# AD_IanFritz.net
KiCad netlist of a schematic drawn in EAGLE
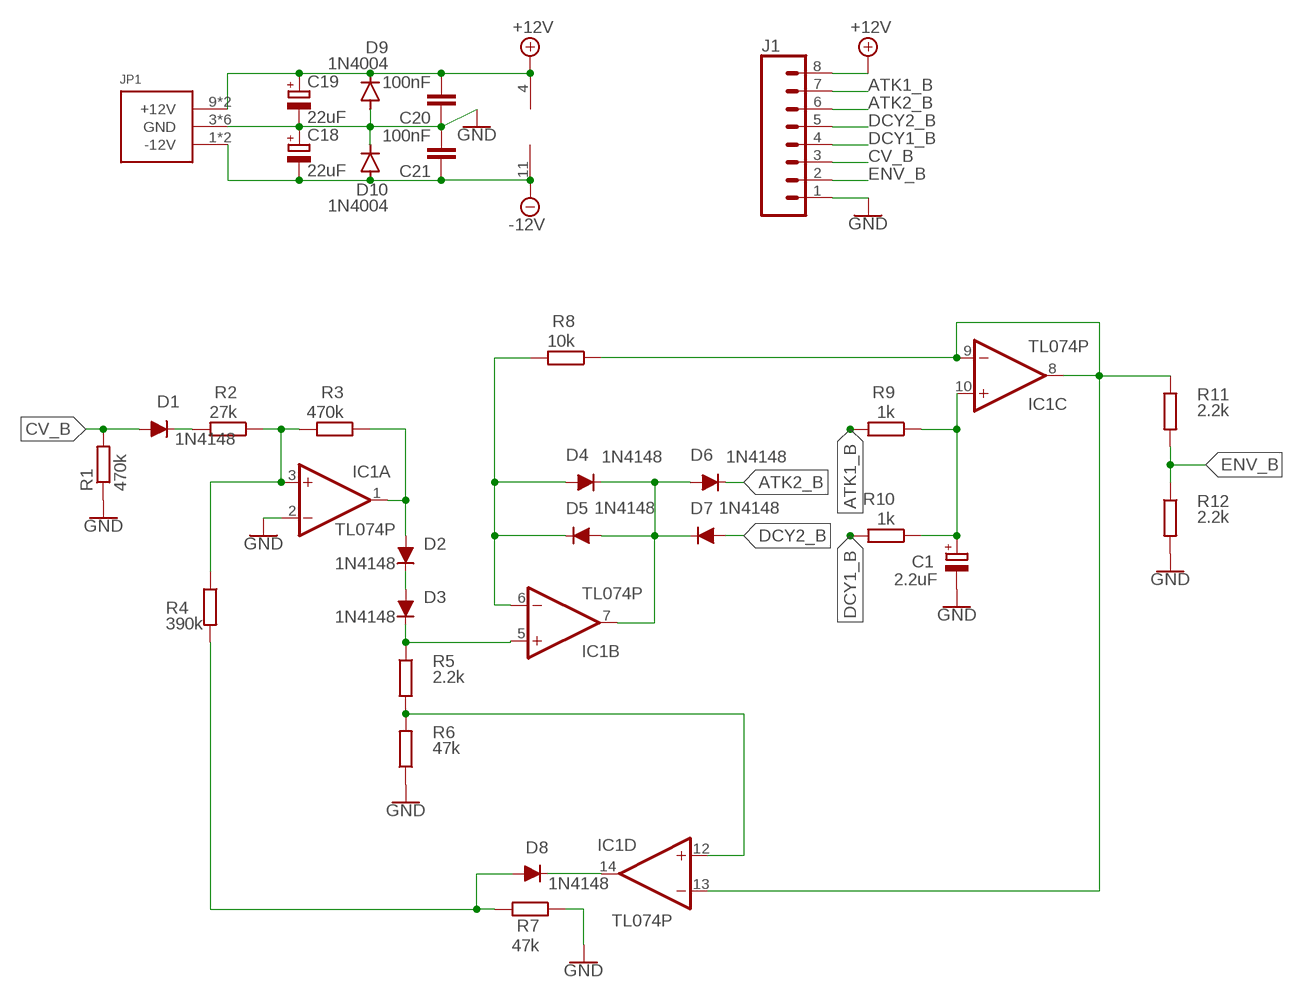
[diagram p0: schematic, sheet 1]

(export (version "E")
  (design (tool "Eeschema 10.0.6"))
  (components
    (comp (ref "C1")
      (value "2.2uF")
      (footprint "eagle-import:E2-4")
      (libsource (lib "eagle-import") (part "CPOL-EUE2-4"))
    )
    (comp (ref "C18")
      (value "22uF")
      (footprint "eagle-import:E2-4")
      (libsource (lib "eagle-import") (part "CPOL-EUE2-4"))
    )
    (comp (ref "C19")
      (value "22uF")
      (footprint "eagle-import:E2-4")
      (libsource (lib "eagle-import") (part "CPOL-EUE2-4"))
    )
    (comp (ref "C20")
      (value "100nF")
      (footprint "eagle-import:C2.5-3")
      (libsource (lib "eagle-import") (part "C2,5-3"))
    )
    (comp (ref "C21")
      (value "100nF")
      (footprint "eagle-import:C2.5-3")
      (libsource (lib "eagle-import") (part "C2,5-3"))
    )
    (comp (ref "D1")
      (value "1N4148")
      (footprint "eagle-import:DO-35")
      (libsource (lib "eagle-import") (part "DIODED0-35"))
    )
    (comp (ref "D2")
      (value "1N4148")
      (footprint "eagle-import:DO-35")
      (libsource (lib "eagle-import") (part "DIODED0-35"))
    )
    (comp (ref "D3")
      (value "1N4148")
      (footprint "eagle-import:DO-35")
      (libsource (lib "eagle-import") (part "DIODED0-35"))
    )
    (comp (ref "D4")
      (value "1N4148")
      (footprint "eagle-import:DO-35")
      (libsource (lib "eagle-import") (part "DIODED0-35"))
    )
    (comp (ref "D5")
      (value "1N4148")
      (footprint "eagle-import:DO-35")
      (libsource (lib "eagle-import") (part "DIODED0-35"))
    )
    (comp (ref "D6")
      (value "1N4148")
      (footprint "eagle-import:DO-35")
      (libsource (lib "eagle-import") (part "DIODED0-35"))
    )
    (comp (ref "D7")
      (value "1N4148")
      (footprint "eagle-import:DO-35")
      (libsource (lib "eagle-import") (part "DIODED0-35"))
    )
    (comp (ref "D8")
      (value "1N4148")
      (footprint "eagle-import:DO-35")
      (libsource (lib "eagle-import") (part "DIODED0-35"))
    )
    (comp (ref "D9")
      (value "1N4004")
      (footprint "eagle-import:DO41-10")
      (libsource (lib "eagle-import") (part "1N4004"))
    )
    (comp (ref "D10")
      (value "1N4004")
      (footprint "eagle-import:DO41-10")
      (libsource (lib "eagle-import") (part "1N4004"))
    )
    (comp (ref "IC1")
      (value "TL074P")
      (footprint "eagle-import:DIL14")
      (libsource (lib "eagle-import") (part "TL074P"))
    )
    (comp (ref "J1")
      (value "CONN_08\"")
      (footprint "eagle-import:1X08")
      (libsource (lib "eagle-import") (part "CONN_08{dblquote}"))
    )
    (comp (ref "JP1")
      (value "POWER_SIMPLE10")
      (footprint "eagle-import:POWER_10")
      (libsource (lib "eagle-import") (part "POWER_SIMPLE10"))
    )
    (comp (ref "R1")
      (value "470k")
      (footprint "eagle-import:7MM_RESISTOR")
      (libsource (lib "eagle-import") (part "RESISTOR7MM"))
    )
    (comp (ref "R2")
      (value "27k")
      (footprint "eagle-import:7MM_RESISTOR")
      (libsource (lib "eagle-import") (part "RESISTOR7MM"))
    )
    (comp (ref "R3")
      (value "470k")
      (footprint "eagle-import:7MM_RESISTOR")
      (libsource (lib "eagle-import") (part "RESISTOR7MM"))
    )
    (comp (ref "R4")
      (value "390k")
      (footprint "eagle-import:7MM_RESISTOR")
      (libsource (lib "eagle-import") (part "RESISTOR7MM"))
    )
    (comp (ref "R5")
      (value "2.2k")
      (footprint "eagle-import:7MM_RESISTOR")
      (libsource (lib "eagle-import") (part "RESISTOR7MM"))
    )
    (comp (ref "R6")
      (value "47k")
      (footprint "eagle-import:7MM_RESISTOR")
      (libsource (lib "eagle-import") (part "RESISTOR7MM"))
    )
    (comp (ref "R7")
      (value "47k")
      (footprint "eagle-import:7MM_RESISTOR")
      (libsource (lib "eagle-import") (part "RESISTOR7MM"))
    )
    (comp (ref "R8")
      (value "10k")
      (footprint "eagle-import:7MM_RESISTOR")
      (libsource (lib "eagle-import") (part "RESISTOR7MM"))
    )
    (comp (ref "R9")
      (value "1k")
      (footprint "eagle-import:7MM_RESISTOR")
      (libsource (lib "eagle-import") (part "RESISTOR7MM"))
    )
    (comp (ref "R10")
      (value "1k")
      (footprint "eagle-import:7MM_RESISTOR")
      (libsource (lib "eagle-import") (part "RESISTOR7MM"))
    )
    (comp (ref "R11")
      (value "2.2k")
      (footprint "eagle-import:7MM_RESISTOR")
      (libsource (lib "eagle-import") (part "RESISTOR7MM"))
    )
    (comp (ref "R12")
      (value "2.2k")
      (footprint "eagle-import:7MM_RESISTOR")
      (libsource (lib "eagle-import") (part "RESISTOR7MM"))
    )
  )
  (nets
    (net (code "1") (name "+12V") (class "Default")
      (node (ref "C19") (pin "+") (pinfunction "+_+") (pintype "passive"))
      (node (ref "C20") (pin "2") (pinfunction "2_2") (pintype "passive"))
      (node (ref "D9") (pin "C") (pinfunction "C_C") (pintype "passive"))
      (node (ref "IC1") (pin "4") (pinfunction "V+_4") (pintype "power_in"))
      (node (ref "J1") (pin "8") (pinfunction "8_8") (pintype "passive"))
      (node (ref "JP1") (pin "10") (pinfunction "+12V_10") (pintype "bidirectional"))
      (node (ref "JP1") (pin "9") (pinfunction "+12V_9") (pintype "bidirectional"))
    )
    (net (code "2") (name "-12V") (class "Default")
      (node (ref "C18") (pin "-") (pinfunction "-_-") (pintype "passive"))
      (node (ref "C21") (pin "1") (pinfunction "1_1") (pintype "passive"))
      (node (ref "D10") (pin "A") (pinfunction "A_A") (pintype "passive"))
      (node (ref "IC1") (pin "11") (pinfunction "V-_11") (pintype "power_in"))
      (node (ref "JP1") (pin "1") (pinfunction "-12V_1") (pintype "bidirectional"))
      (node (ref "JP1") (pin "2") (pinfunction "-12V_2") (pintype "bidirectional"))
    )
    (net (code "3") (name "ATK1_B") (class "Default")
      (node (ref "J1") (pin "7") (pinfunction "7_7") (pintype "passive"))
      (node (ref "R9") (pin "2") (pinfunction "2_2") (pintype "passive"))
    )
    (net (code "4") (name "ATK2_B") (class "Default")
      (node (ref "D6") (pin "C") (pinfunction "C_C") (pintype "passive"))
      (node (ref "J1") (pin "6") (pinfunction "6_6") (pintype "passive"))
    )
    (net (code "5") (name "CV_B") (class "Default")
      (node (ref "D1") (pin "A") (pinfunction "A_A") (pintype "passive"))
      (node (ref "J1") (pin "3") (pinfunction "3_3") (pintype "passive"))
      (node (ref "R1") (pin "2") (pinfunction "2_2") (pintype "passive"))
    )
    (net (code "6") (name "DCY1_B") (class "Default")
      (node (ref "J1") (pin "4") (pinfunction "4_4") (pintype "passive"))
      (node (ref "R10") (pin "2") (pinfunction "2_2") (pintype "passive"))
    )
    (net (code "7") (name "DCY2_B") (class "Default")
      (node (ref "D7") (pin "A") (pinfunction "A_A") (pintype "passive"))
      (node (ref "J1") (pin "5") (pinfunction "5_5") (pintype "passive"))
    )
    (net (code "8") (name "ENV_B") (class "Default")
      (node (ref "J1") (pin "2") (pinfunction "2_2") (pintype "passive"))
      (node (ref "R11") (pin "2") (pinfunction "2_2") (pintype "passive"))
      (node (ref "R12") (pin "1") (pinfunction "1_1") (pintype "passive"))
    )
    (net (code "9") (name "GND") (class "Default")
      (node (ref "C1") (pin "-") (pinfunction "-_-") (pintype "passive"))
      (node (ref "C18") (pin "+") (pinfunction "+_+") (pintype "passive"))
      (node (ref "C19") (pin "-") (pinfunction "-_-") (pintype "passive"))
      (node (ref "C20") (pin "1") (pinfunction "1_1") (pintype "passive"))
      (node (ref "C21") (pin "2") (pinfunction "2_2") (pintype "passive"))
      (node (ref "D10") (pin "C") (pinfunction "C_C") (pintype "passive"))
      (node (ref "D9") (pin "A") (pinfunction "A_A") (pintype "passive"))
      (node (ref "IC1") (pin "2") (pinfunction "-IN_2") (pintype "input"))
      (node (ref "J1") (pin "1") (pinfunction "1_1") (pintype "passive"))
      (node (ref "JP1") (pin "3") (pinfunction "GND_3") (pintype "bidirectional"))
      (node (ref "JP1") (pin "4") (pinfunction "GND_4") (pintype "bidirectional"))
      (node (ref "JP1") (pin "5") (pinfunction "GND_5") (pintype "bidirectional"))
      (node (ref "JP1") (pin "6") (pinfunction "GND_6") (pintype "bidirectional"))
      (node (ref "JP1") (pin "7") (pinfunction "GND_7") (pintype "bidirectional"))
      (node (ref "JP1") (pin "8") (pinfunction "GND_8") (pintype "bidirectional"))
      (node (ref "R1") (pin "1") (pinfunction "1_1") (pintype "passive"))
      (node (ref "R12") (pin "2") (pinfunction "2_2") (pintype "passive"))
      (node (ref "R6") (pin "1") (pinfunction "1_1") (pintype "passive"))
      (node (ref "R7") (pin "1") (pinfunction "1_1") (pintype "passive"))
    )
    (net (code "10") (name "Net-(D1-PadC)") (class "Default")
      (node (ref "D1") (pin "C") (pinfunction "C_C") (pintype "passive"))
      (node (ref "R2") (pin "2") (pinfunction "2_2") (pintype "passive"))
    )
    (net (code "11") (name "Net-(D2-PadC)") (class "Default")
      (node (ref "D2") (pin "C") (pinfunction "C_C") (pintype "passive"))
      (node (ref "D3") (pin "A") (pinfunction "A_A") (pintype "passive"))
    )
    (net (code "12") (name "Net-(D8-PadA)") (class "Default")
      (node (ref "D8") (pin "A") (pinfunction "A_A") (pintype "passive"))
      (node (ref "R4") (pin "2") (pinfunction "2_2") (pintype "passive"))
      (node (ref "R7") (pin "2") (pinfunction "2_2") (pintype "passive"))
    )
    (net (code "13") (name "Net-(IC1A-+IN)") (class "Default")
      (node (ref "IC1") (pin "3") (pinfunction "+IN_3") (pintype "input"))
      (node (ref "R2") (pin "1") (pinfunction "1_1") (pintype "passive"))
      (node (ref "R3") (pin "2") (pinfunction "2_2") (pintype "passive"))
      (node (ref "R4") (pin "1") (pinfunction "1_1") (pintype "passive"))
    )
    (net (code "14") (name "Net-(IC1A-OUT)") (class "Default")
      (node (ref "D2") (pin "A") (pinfunction "A_A") (pintype "passive"))
      (node (ref "IC1") (pin "1") (pinfunction "OUT_1") (pintype "output"))
      (node (ref "R3") (pin "1") (pinfunction "1_1") (pintype "passive"))
    )
    (net (code "15") (name "Net-(IC1B-+IN)") (class "Default")
      (node (ref "D3") (pin "C") (pinfunction "C_C") (pintype "passive"))
      (node (ref "IC1") (pin "5") (pinfunction "+IN_5") (pintype "input"))
      (node (ref "R5") (pin "1") (pinfunction "1_1") (pintype "passive"))
    )
    (net (code "16") (name "Net-(IC1B--IN)") (class "Default")
      (node (ref "D4") (pin "A") (pinfunction "A_A") (pintype "passive"))
      (node (ref "D5") (pin "C") (pinfunction "C_C") (pintype "passive"))
      (node (ref "IC1") (pin "6") (pinfunction "-IN_6") (pintype "input"))
      (node (ref "R8") (pin "2") (pinfunction "2_2") (pintype "passive"))
    )
    (net (code "17") (name "Net-(IC1B-OUT)") (class "Default")
      (node (ref "D4") (pin "C") (pinfunction "C_C") (pintype "passive"))
      (node (ref "D5") (pin "A") (pinfunction "A_A") (pintype "passive"))
      (node (ref "D6") (pin "A") (pinfunction "A_A") (pintype "passive"))
      (node (ref "D7") (pin "C") (pinfunction "C_C") (pintype "passive"))
      (node (ref "IC1") (pin "7") (pinfunction "OUT_7") (pintype "output"))
    )
    (net (code "18") (name "Net-(IC1C-+IN)") (class "Default")
      (node (ref "C1") (pin "+") (pinfunction "+_+") (pintype "passive"))
      (node (ref "IC1") (pin "10") (pinfunction "+IN_10") (pintype "input"))
      (node (ref "R10") (pin "1") (pinfunction "1_1") (pintype "passive"))
      (node (ref "R9") (pin "1") (pinfunction "1_1") (pintype "passive"))
    )
    (net (code "19") (name "Net-(IC1C--IN)") (class "Default")
      (node (ref "IC1") (pin "13") (pinfunction "-IN_13") (pintype "input"))
      (node (ref "IC1") (pin "8") (pinfunction "OUT_8") (pintype "output"))
      (node (ref "IC1") (pin "9") (pinfunction "-IN_9") (pintype "input"))
      (node (ref "R11") (pin "1") (pinfunction "1_1") (pintype "passive"))
      (node (ref "R8") (pin "1") (pinfunction "1_1") (pintype "passive"))
    )
    (net (code "20") (name "Net-(IC1D-+IN)") (class "Default")
      (node (ref "IC1") (pin "12") (pinfunction "+IN_12") (pintype "input"))
      (node (ref "R5") (pin "2") (pinfunction "2_2") (pintype "passive"))
      (node (ref "R6") (pin "2") (pinfunction "2_2") (pintype "passive"))
    )
    (net (code "21") (name "Net-(IC1D-OUT)") (class "Default")
      (node (ref "D8") (pin "C") (pinfunction "C_C") (pintype "passive"))
      (node (ref "IC1") (pin "14") (pinfunction "OUT_14") (pintype "output"))
    )
  )
)
